# Dimmer.net
KiCad netlist of a schematic drawn in Altium Designer
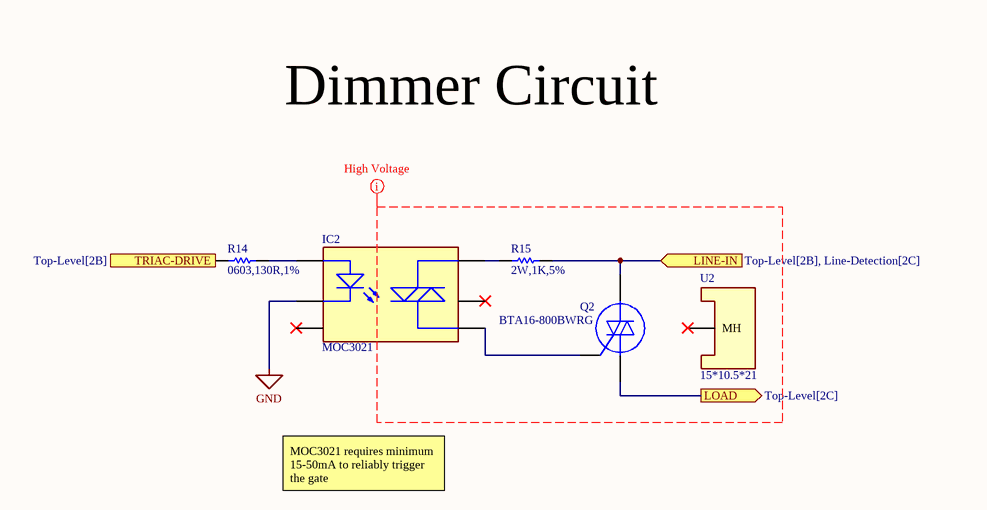
[diagram p0: Dimmer.SchDoc]

(export (version "E")
  (design (tool "Eeschema 10.0.6"))
  (components
    (comp (ref "IC2")
      (value "MOC3021")
      (footprint "DIP-6_L8.5-W6.4-P2.54-LS7.6-BL")
      (description "1000V/us 50mA 400V 1.15V TRIAC DIP-6 Triac, SCR Output Optoisolators ROHS")
      (fields
        (field (name "MANUFACTURER_PART_NUMBER") "MOC3020")
        (field (name "MOUSER PART NUMBER") "859-MOC3020")
      )
      (libsource (lib "LC-SchLib") (part "MOC3021"))
    )
    (comp (ref "Q2")
      (value "BTA16-800BWRG")
      (footprint "TO255P1020X450X1965-3")
      (description "35mA 50mA 800V 1 TRIAC TO-220AB Thyristors (SCR)/Modules ROHS")
      (fields
        (field (name "MOUSER PART NUMBER") "511-BTA16-800BW")
        (field (name "LCSC PART NUMBER") "C10065")
      )
      (libsource (lib "LC-SchLib") (part "BTA16-800BWRG"))
    )
    (comp (ref "R14")
      (value "0603,130R,1%")
      (footprint "RESC1608X55N")
      (description "130 Ohms ±1% 0.1W, 1/10W Chip Resistor 0603 (1608 Metric) Moisture Resistant Thick Film")
      (fields
        (field (name "MANUFACTURER_PART_NUMBER") "RC0603FR-07130RL")
        (field (name "LCSC PART NUMBER") "C141677")
      )
      (libsource (lib "LC-SchLib") (part "RC0603FR-07130RL"))
    )
    (comp (ref "R15")
      (value "2W,1K,5%")
      (footprint "RES-TH_BD4.0-L11.5-P15.50-D0.7")
      (description "Metal Film Resistor 1kΩ 2W ±5% Through Hole,D3.9xL9mm Through Hole Resistors ROHS")
      (fields (field (name "LCSC PART NUMBER") "C1740167"))
      (libsource (lib "LC-SchLib") (part "FMP200JR-52-1K"))
    )
    (comp (ref "U2")
      (value "15*10.5*21")
      (footprint "SINK-TH_L15.0-W10.5-H21.0")
      (description "15.5*10.5*21MM 6063-T5 Heat sink / cooling fin ROHS")
      (fields (field (name "LCSC PART NUMBER") "C7421513"))
      (libsource (lib "LC-SchLib") (part "15*10.5*21"))
    )
  )
  (nets
    (net (code "1") (name "/LINE-IN") (class "Default")
      (node (ref "Q2") (pin "2") (pinfunction "A2_2") (pintype "passive"))
      (node (ref "R15") (pin "2") (pinfunction "2_2") (pintype "passive"))
    )
    (net (code "2") (name "/LOAD") (class "Default")
      (node (ref "Q2") (pin "1") (pinfunction "A1_1") (pintype "passive"))
    )
    (net (code "3") (name "/TRIAC-DRIVE") (class "Default")
      (node (ref "R14") (pin "1") (pinfunction "1_1") (pintype "passive"))
    )
    (net (code "4") (name "GND") (class "Default")
      (node (ref "IC2") (pin "2") (pinfunction "CATHODE_2") (pintype "passive"))
    )
    (net (code "5") (name "Net-(IC2-ANODE)") (class "Default")
      (node (ref "IC2") (pin "1") (pinfunction "ANODE_1") (pintype "passive"))
      (node (ref "R14") (pin "2") (pinfunction "2_2") (pintype "passive"))
    )
    (net (code "6") (name "Net-(IC2-MAIN_TERMINAL_1)") (class "Default")
      (node (ref "IC2") (pin "4") (pinfunction "MAIN_TERMINAL_1_4") (pintype "passive"))
      (node (ref "Q2") (pin "3") (pinfunction "G_3") (pintype "passive"))
    )
    (net (code "7") (name "Net-(IC2-MAIN_TERMINAL_2)") (class "Default")
      (node (ref "IC2") (pin "6") (pinfunction "MAIN_TERMINAL_2_6") (pintype "passive"))
      (node (ref "R15") (pin "1") (pinfunction "1_1") (pintype "passive"))
    )
    (net (code "8") (name "unconnected-(IC2-NC-Pad3)") (class "Default")
      (node (ref "IC2") (pin "3") (pinfunction "NC_3") (pintype "passive+no_connect"))
    )
    (net (code "9") (name "unconnected-(IC2-SUBSTRATE-Pad5)") (class "Default")
      (node (ref "IC2") (pin "5") (pinfunction "SUBSTRATE_5") (pintype "passive+no_connect"))
    )
    (net (code "10") (name "unconnected-(U2-MH-Pad1)") (class "Default")
      (node (ref "U2") (pin "1") (pinfunction "MH_1") (pintype "passive+no_connect"))
    )
  )
)
